# HydraBus_1_0_Rev1_1.net
KiCad netlist of a schematic drawn in EAGLE
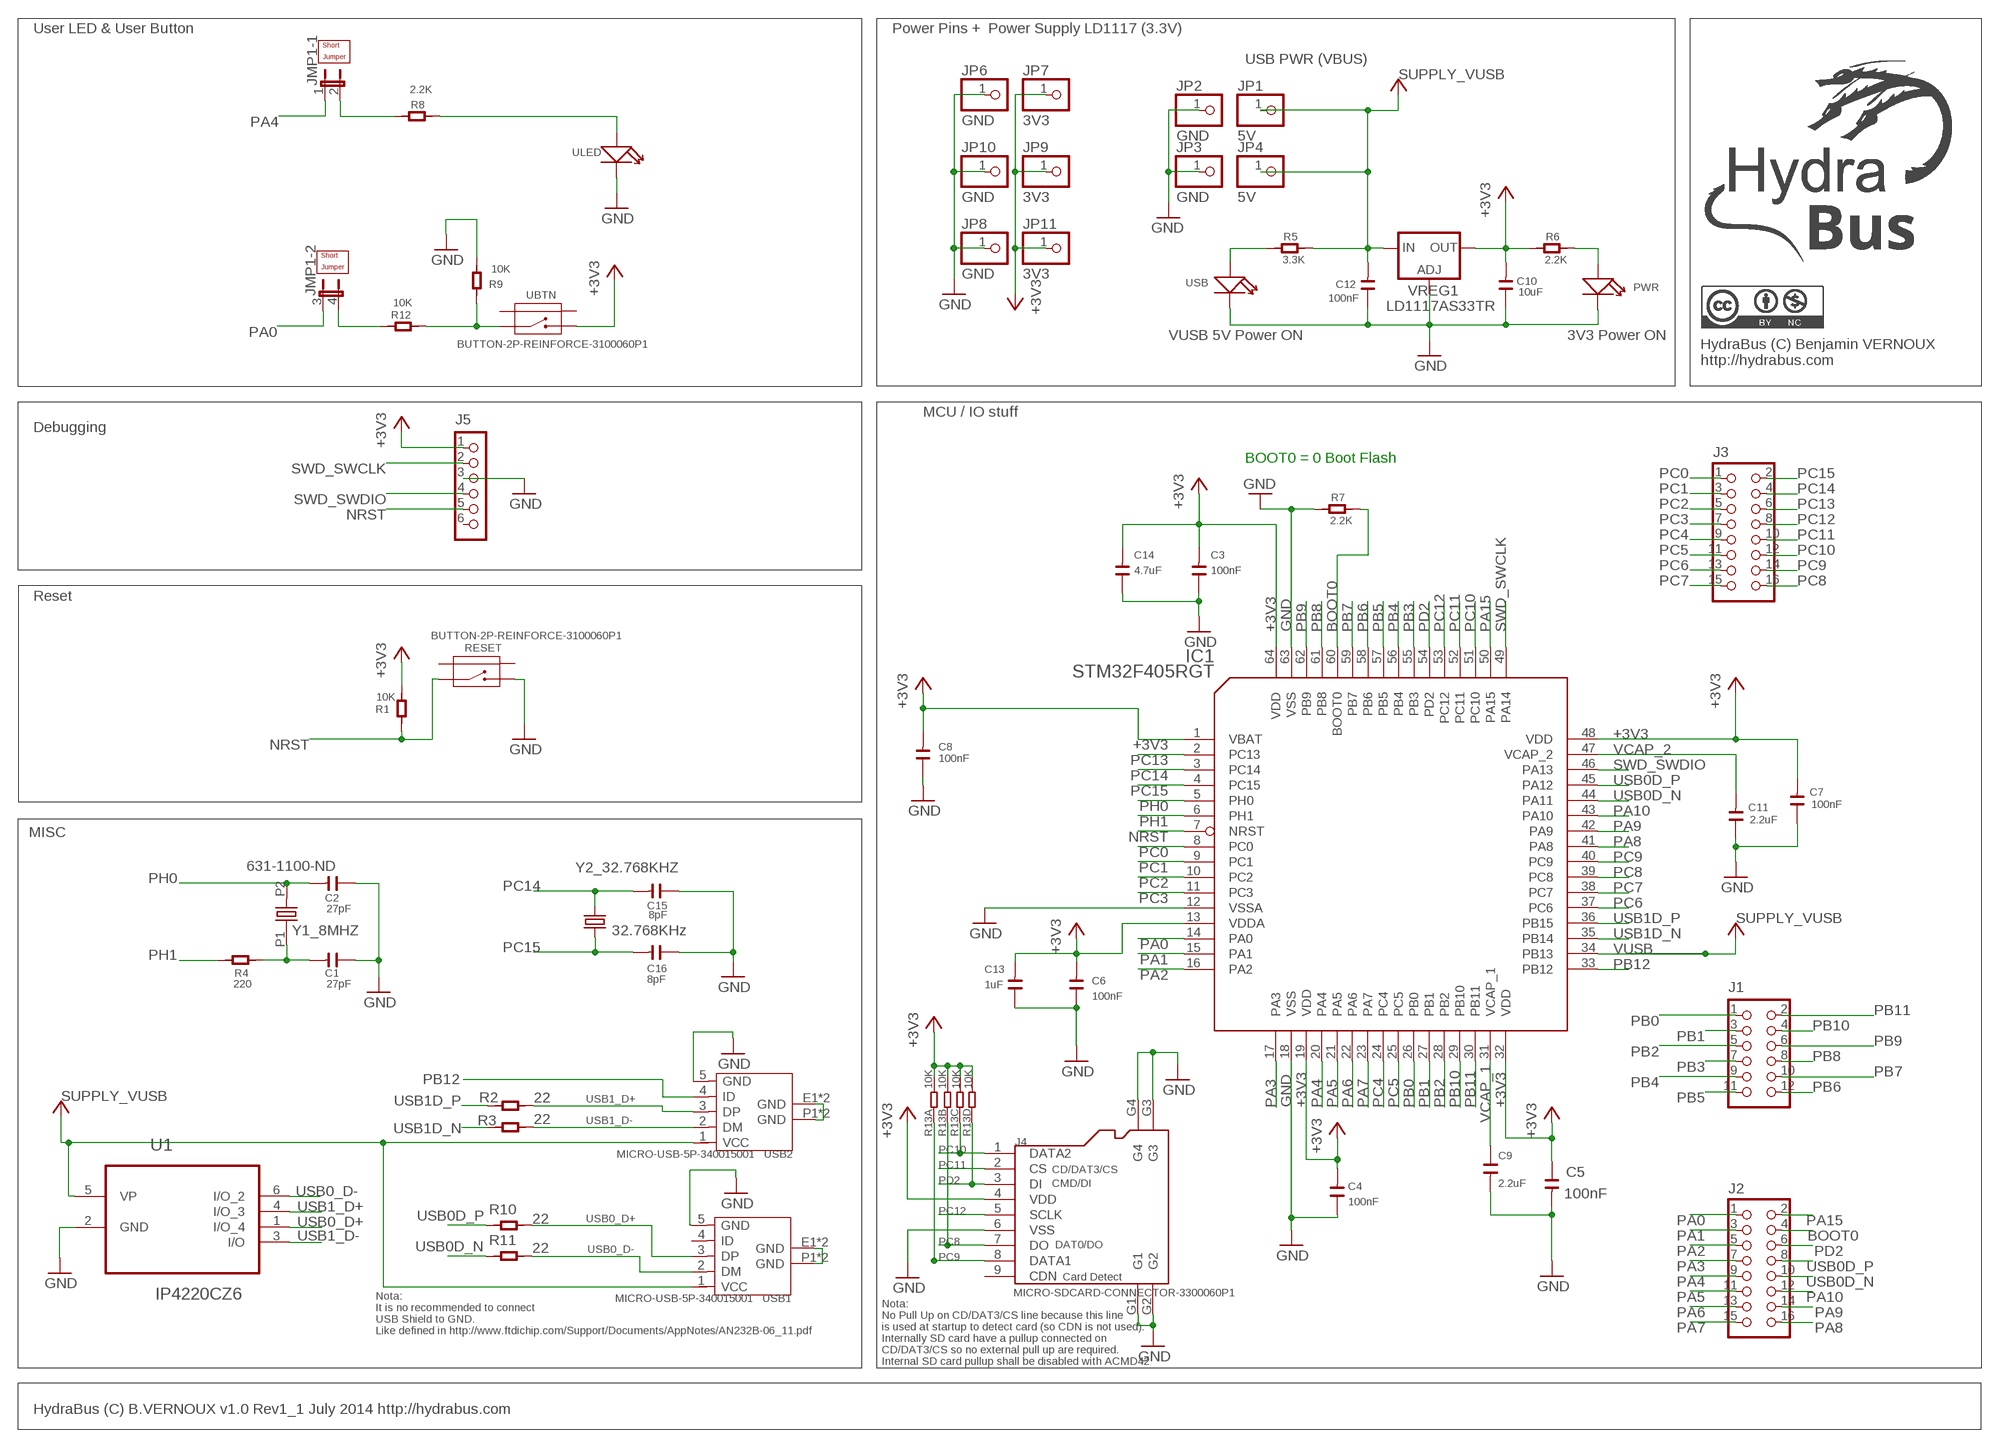
[diagram p0: schematic, sheet 1]

(export (version "E")
  (design (tool "Eeschema 10.0.6"))
  (components
    (comp (ref "C1")
      (value "27pF")
      (footprint "eagle-import:C0603")
      (libsource (lib "eagle-import") (part "C-0603"))
    )
    (comp (ref "C2")
      (value "27pF")
      (footprint "eagle-import:C0603")
      (libsource (lib "eagle-import") (part "C-0603"))
    )
    (comp (ref "C3")
      (value "100nF")
      (footprint "eagle-import:C0603")
      (libsource (lib "eagle-import") (part "C-0603"))
    )
    (comp (ref "C4")
      (value "100nF")
      (footprint "eagle-import:C0603")
      (libsource (lib "eagle-import") (part "C-0603"))
    )
    (comp (ref "C5")
      (value "100nF")
      (footprint "eagle-import:C0603")
      (libsource (lib "eagle-import") (part "C-0603"))
    )
    (comp (ref "C6")
      (value "100nF")
      (footprint "eagle-import:C0603")
      (libsource (lib "eagle-import") (part "C-0603"))
    )
    (comp (ref "C7")
      (value "100nF")
      (footprint "eagle-import:C0603")
      (libsource (lib "eagle-import") (part "C-0603"))
    )
    (comp (ref "C8")
      (value "100nF")
      (footprint "eagle-import:C0603")
      (libsource (lib "eagle-import") (part "C-0603"))
    )
    (comp (ref "C9")
      (value "2.2uF")
      (footprint "eagle-import:C0603")
      (libsource (lib "eagle-import") (part "C-0603"))
    )
    (comp (ref "C10")
      (value "10uF")
      (footprint "eagle-import:C0805")
      (libsource (lib "eagle-import") (part "C-0805"))
    )
    (comp (ref "C11")
      (value "2.2uF")
      (footprint "eagle-import:C0603")
      (libsource (lib "eagle-import") (part "C-0603"))
    )
    (comp (ref "C12")
      (value "100nF")
      (footprint "eagle-import:C0603")
      (libsource (lib "eagle-import") (part "C-0603"))
    )
    (comp (ref "C13")
      (value "1uF")
      (footprint "eagle-import:C0603")
      (libsource (lib "eagle-import") (part "C-0603"))
    )
    (comp (ref "C14")
      (value "4.7uF")
      (footprint "eagle-import:C0603")
      (libsource (lib "eagle-import") (part "C-0603"))
    )
    (comp (ref "C15")
      (value "8pF")
      (footprint "eagle-import:C0603")
      (libsource (lib "eagle-import") (part "C-0603"))
    )
    (comp (ref "C16")
      (value "8pF")
      (footprint "eagle-import:C0603")
      (libsource (lib "eagle-import") (part "C-0603"))
    )
    (comp (ref "IC1")
      (value "STM32F405RGT")
      (footprint "eagle-import:LQFP64")
      (libsource (lib "eagle-import") (part "STM32F405RTG"))
    )
    (comp (ref "J1")
      (value "CON_HEADER_2X06")
      (footprint "eagle-import:M2X6")
      (libsource (lib "eagle-import") (part "CON_HEADER_2X06"))
    )
    (comp (ref "J2")
      (value "CON_HEADER_2X08")
      (footprint "eagle-import:M2X8")
      (libsource (lib "eagle-import") (part "CON_HEADER_2X08"))
    )
    (comp (ref "J3")
      (value "CON_HEADER_2X08")
      (footprint "eagle-import:M2X8")
      (libsource (lib "eagle-import") (part "CON_HEADER_2X08"))
    )
    (comp (ref "J4")
      (value "MICRO-SDCARD-CONNECTOR-3300060P1")
      (footprint "eagle-import:9P-SMD-W-RING")
      (libsource (lib "eagle-import") (part "MICRO-SDCARD-CONNECTOR-3300060P1"))
    )
    (comp (ref "J5")
      (value "CON_HEADER_1X06-PTH")
      (footprint "eagle-import:M1X6")
      (libsource (lib "eagle-import") (part "CON_HEADER_1X06-PTH"))
    )
    (comp (ref "JMP1")
      (value "JP2QE")
      (footprint "eagle-import:JP2Q")
      (libsource (lib "eagle-import") (part "JP2QE"))
    )
    (comp (ref "JMP_UBTN")
      (value "SHORT-JUMPER-2P-3460440P1")
      (footprint "eagle-import:2P-2.54")
      (libsource (lib "eagle-import") (part "SHORT-JUMPER-2P-3460440P1"))
    )
    (comp (ref "JMP_ULED")
      (value "SHORT-JUMPER-2P-3460440P1")
      (footprint "eagle-import:2P-2.54")
      (libsource (lib "eagle-import") (part "SHORT-JUMPER-2P-3460440P1"))
    )
    (comp (ref "JP1")
      (value "5V")
      (footprint "eagle-import:1X01")
      (libsource (lib "eagle-import") (part "PINHD-1X1"))
    )
    (comp (ref "JP2")
      (value "GND")
      (footprint "eagle-import:1X01")
      (libsource (lib "eagle-import") (part "PINHD-1X1"))
    )
    (comp (ref "JP3")
      (value "GND")
      (footprint "eagle-import:1X01")
      (libsource (lib "eagle-import") (part "PINHD-1X1"))
    )
    (comp (ref "JP4")
      (value "5V")
      (footprint "eagle-import:1X01")
      (libsource (lib "eagle-import") (part "PINHD-1X1"))
    )
    (comp (ref "JP6")
      (value "GND")
      (footprint "eagle-import:1X01")
      (libsource (lib "eagle-import") (part "PINHD-1X1"))
    )
    (comp (ref "JP7")
      (value "3V3")
      (footprint "eagle-import:1X01")
      (libsource (lib "eagle-import") (part "PINHD-1X1"))
    )
    (comp (ref "JP8")
      (value "GND")
      (footprint "eagle-import:1X01")
      (libsource (lib "eagle-import") (part "PINHD-1X1"))
    )
    (comp (ref "JP9")
      (value "3V3")
      (footprint "eagle-import:1X01")
      (libsource (lib "eagle-import") (part "PINHD-1X1"))
    )
    (comp (ref "JP10")
      (value "GND")
      (footprint "eagle-import:1X01")
      (libsource (lib "eagle-import") (part "PINHD-1X1"))
    )
    (comp (ref "JP11")
      (value "3V3")
      (footprint "eagle-import:1X01")
      (libsource (lib "eagle-import") (part "PINHD-1X1"))
    )
    (comp (ref "PWR")
      (value "LED")
      (footprint "eagle-import:LED0603")
      (libsource (lib "eagle-import") (part "LED"))
    )
    (comp (ref "R1")
      (value "10K")
      (footprint "eagle-import:R0603")
      (libsource (lib "eagle-import") (part "R-0603"))
    )
    (comp (ref "R2")
      (value "22")
      (footprint "eagle-import:R0603")
      (libsource (lib "eagle-import") (part "R-0603"))
    )
    (comp (ref "R3")
      (value "22")
      (footprint "eagle-import:R0603")
      (libsource (lib "eagle-import") (part "R-0603"))
    )
    (comp (ref "R4")
      (value "220")
      (footprint "eagle-import:R0603")
      (libsource (lib "eagle-import") (part "R-0603"))
    )
    (comp (ref "R5")
      (value "3.3K")
      (footprint "eagle-import:R0603")
      (libsource (lib "eagle-import") (part "R-0603"))
    )
    (comp (ref "R6")
      (value "2.2K")
      (footprint "eagle-import:R0603")
      (libsource (lib "eagle-import") (part "R-0603"))
    )
    (comp (ref "R7")
      (value "2.2K")
      (footprint "eagle-import:R0603")
      (libsource (lib "eagle-import") (part "R-0603"))
    )
    (comp (ref "R8")
      (value "2.2K")
      (footprint "eagle-import:R0603")
      (libsource (lib "eagle-import") (part "R-0603"))
    )
    (comp (ref "R9")
      (value "10K")
      (footprint "eagle-import:R0603")
      (libsource (lib "eagle-import") (part "R-0603"))
    )
    (comp (ref "R10")
      (value "22")
      (footprint "eagle-import:R0603")
      (libsource (lib "eagle-import") (part "R-0603"))
    )
    (comp (ref "R11")
      (value "22")
      (footprint "eagle-import:R0603")
      (libsource (lib "eagle-import") (part "R-0603"))
    )
    (comp (ref "R12")
      (value "10K")
      (footprint "eagle-import:R0603")
      (libsource (lib "eagle-import") (part "R-0603"))
    )
    (comp (ref "R13")
      (value "10K")
      (footprint "eagle-import:R1206-8")
      (fields (field (name "OPL") "0040070P1 SMD RES ARRAY 10K OHM 4 RES 1206"))
      (libsource (lib "eagle-import") (part "R-4R"))
    )
    (comp (ref "RESET")
      (value "BUTTON-2P-REINFORCE-3100060P1")
      (footprint "eagle-import:4P-SMD-7.0X3.5X3.5H-90D")
      (libsource (lib "eagle-import") (part "BUTTON-2P-REINFORCE-3100060P1"))
    )
    (comp (ref "U1")
      (value "IP4220CZ6")
      (footprint "eagle-import:SOT95P275X110-6N")
      (libsource (lib "eagle-import") (part "IP4220CZ6"))
    )
    (comp (ref "UBTN")
      (value "BUTTON-2P-REINFORCE-3100060P1")
      (footprint "eagle-import:4P-SMD-7.0X3.5X3.5H-90D")
      (libsource (lib "eagle-import") (part "BUTTON-2P-REINFORCE-3100060P1"))
    )
    (comp (ref "ULED")
      (value "LED")
      (footprint "eagle-import:LED0603")
      (libsource (lib "eagle-import") (part "LED"))
    )
    (comp (ref "USB")
      (value "LED")
      (footprint "eagle-import:LED0603")
      (libsource (lib "eagle-import") (part "LED"))
    )
    (comp (ref "USB1")
      (value "MICRO-USB-5P-340015001")
      (footprint "eagle-import:B-SMD-5P")
      (libsource (lib "eagle-import") (part "MICRO-USB-5P-340015001"))
    )
    (comp (ref "USB2")
      (value "MICRO-USB-5P-340015001")
      (footprint "eagle-import:B-SMD-5P")
      (libsource (lib "eagle-import") (part "MICRO-USB-5P-340015001"))
    )
    (comp (ref "VREG1")
      (value "LD1117AS33TR")
      (footprint "eagle-import:SOT223")
      (libsource (lib "eagle-import") (part "LD117A?S33TR"))
    )
    (comp (ref "Y1_8MHZ")
      (value "631-1100-ND")
      (footprint "eagle-import:HC-49U-PTH")
      (libsource (lib "eagle-import") (part "OSC-XTAL-HC-49U-PTH"))
    )
    (comp (ref "Y2_32.768KHZ")
      (value "32.768KHz")
      (footprint "eagle-import:TC38H")
      (libsource (lib "eagle-import") (part "CRYSTALTC38H"))
    )
  )
  (nets
    (net (code "1") (name "+3V3") (class "Default")
      (node (ref "C10") (pin "1") (pinfunction "1_1") (pintype "bidirectional"))
      (node (ref "C13") (pin "1") (pinfunction "1_1") (pintype "bidirectional"))
      (node (ref "C14") (pin "1") (pinfunction "1_1") (pintype "bidirectional"))
      (node (ref "C3") (pin "1") (pinfunction "1_1") (pintype "bidirectional"))
      (node (ref "C4") (pin "1") (pinfunction "1_1") (pintype "bidirectional"))
      (node (ref "C5") (pin "2") (pinfunction "2_2") (pintype "bidirectional"))
      (node (ref "C6") (pin "1") (pinfunction "1_1") (pintype "bidirectional"))
      (node (ref "C7") (pin "1") (pinfunction "1_1") (pintype "bidirectional"))
      (node (ref "C8") (pin "1") (pinfunction "1_1") (pintype "bidirectional"))
      (node (ref "IC1") (pin "1") (pinfunction "VBAT_1") (pintype "power_in"))
      (node (ref "IC1") (pin "13") (pinfunction "VDDA_13") (pintype "power_in"))
      (node (ref "IC1") (pin "19") (pinfunction "VDD_19") (pintype "power_in"))
      (node (ref "IC1") (pin "32") (pinfunction "VDD_32") (pintype "power_in"))
      (node (ref "IC1") (pin "48") (pinfunction "VDD_48") (pintype "power_in"))
      (node (ref "IC1") (pin "64") (pinfunction "VDD_64") (pintype "power_in"))
      (node (ref "J4") (pin "4") (pinfunction "VDD_4") (pintype "bidirectional"))
      (node (ref "J5") (pin "1") (pinfunction "1_1") (pintype "bidirectional"))
      (node (ref "JP11") (pin "1") (pinfunction "1_1") (pintype "passive"))
      (node (ref "JP7") (pin "1") (pinfunction "1_1") (pintype "passive"))
      (node (ref "JP9") (pin "1") (pinfunction "1_1") (pintype "passive"))
      (node (ref "R1") (pin "2") (pinfunction "2_2") (pintype "bidirectional"))
      (node (ref "R13") (pin "5") (pinfunction "2_5") (pintype "passive"))
      (node (ref "R13") (pin "6") (pinfunction "2_6") (pintype "passive"))
      (node (ref "R13") (pin "7") (pinfunction "2_7") (pintype "passive"))
      (node (ref "R13") (pin "8") (pinfunction "2_8") (pintype "passive"))
      (node (ref "R6") (pin "2") (pinfunction "2_2") (pintype "bidirectional"))
      (node (ref "UBTN") (pin "2") (pinfunction "2_2") (pintype "bidirectional"))
      (node (ref "VREG1") (pin "4") (pinfunction "OUT_4") (pintype "passive"))
    )
    (net (code "2") (name "/BOOT0") (class "Default")
      (node (ref "IC1") (pin "60") (pinfunction "BOOT0_60") (pintype "bidirectional"))
      (node (ref "J2") (pin "4") (pinfunction "4_4") (pintype "passive"))
      (node (ref "R7") (pin "1") (pinfunction "1_1") (pintype "bidirectional"))
    )
    (net (code "3") (name "/NRST") (class "Default")
      (node (ref "IC1") (pin "7") (pinfunction "NRST_7") (pintype "input"))
      (node (ref "J5") (pin "5") (pinfunction "5_5") (pintype "passive"))
      (node (ref "R1") (pin "1") (pinfunction "1_1") (pintype "bidirectional"))
      (node (ref "RESET") (pin "1") (pinfunction "1_1") (pintype "bidirectional"))
    )
    (net (code "4") (name "/PA0") (class "Default")
      (node (ref "IC1") (pin "14") (pinfunction "PA0_14") (pintype "bidirectional"))
      (node (ref "J2") (pin "1") (pinfunction "1_1") (pintype "passive"))
      (node (ref "JMP1") (pin "3") (pinfunction "1_3") (pintype "passive"))
    )
    (net (code "5") (name "/PA1") (class "Default")
      (node (ref "IC1") (pin "15") (pinfunction "PA1_15") (pintype "bidirectional"))
      (node (ref "J2") (pin "3") (pinfunction "3_3") (pintype "passive"))
    )
    (net (code "6") (name "/PA2") (class "Default")
      (node (ref "IC1") (pin "16") (pinfunction "PA2_16") (pintype "bidirectional"))
      (node (ref "J2") (pin "5") (pinfunction "5_5") (pintype "passive"))
    )
    (net (code "7") (name "/PA3") (class "Default")
      (node (ref "IC1") (pin "17") (pinfunction "PA3_17") (pintype "bidirectional"))
      (node (ref "J2") (pin "7") (pinfunction "7_7") (pintype "passive"))
    )
    (net (code "8") (name "/PA4") (class "Default")
      (node (ref "IC1") (pin "20") (pinfunction "PA4_20") (pintype "bidirectional"))
      (node (ref "J2") (pin "9") (pinfunction "9_9") (pintype "passive"))
      (node (ref "JMP1") (pin "1") (pinfunction "1_1") (pintype "passive"))
    )
    (net (code "9") (name "/PA5") (class "Default")
      (node (ref "IC1") (pin "21") (pinfunction "PA5_21") (pintype "bidirectional"))
      (node (ref "J2") (pin "11") (pinfunction "11_11") (pintype "passive"))
    )
    (net (code "10") (name "/PA6") (class "Default")
      (node (ref "IC1") (pin "22") (pinfunction "PA6_22") (pintype "bidirectional"))
      (node (ref "J2") (pin "13") (pinfunction "13_13") (pintype "passive"))
    )
    (net (code "11") (name "/PA7") (class "Default")
      (node (ref "IC1") (pin "23") (pinfunction "PA7_23") (pintype "bidirectional"))
      (node (ref "J2") (pin "15") (pinfunction "15_15") (pintype "passive"))
    )
    (net (code "12") (name "/PA8") (class "Default")
      (node (ref "IC1") (pin "41") (pinfunction "PA8_41") (pintype "bidirectional"))
      (node (ref "J2") (pin "16") (pinfunction "16_16") (pintype "passive"))
    )
    (net (code "13") (name "/PA9") (class "Default")
      (node (ref "IC1") (pin "42") (pinfunction "PA9_42") (pintype "bidirectional"))
      (node (ref "J2") (pin "14") (pinfunction "14_14") (pintype "passive"))
    )
    (net (code "14") (name "/PA10") (class "Default")
      (node (ref "IC1") (pin "43") (pinfunction "PA10_43") (pintype "bidirectional"))
      (node (ref "J2") (pin "12") (pinfunction "12_12") (pintype "passive"))
    )
    (net (code "15") (name "/PA15") (class "Default")
      (node (ref "IC1") (pin "50") (pinfunction "PA15_50") (pintype "bidirectional"))
      (node (ref "J2") (pin "2") (pinfunction "2_2") (pintype "passive"))
    )
    (net (code "16") (name "/PB0") (class "Default")
      (node (ref "IC1") (pin "26") (pinfunction "PB0_26") (pintype "bidirectional"))
      (node (ref "J1") (pin "1") (pinfunction "1_1") (pintype "passive"))
    )
    (net (code "17") (name "/PB1") (class "Default")
      (node (ref "IC1") (pin "27") (pinfunction "PB1_27") (pintype "bidirectional"))
      (node (ref "J1") (pin "3") (pinfunction "3_3") (pintype "passive"))
    )
    (net (code "18") (name "/PB2") (class "Default")
      (node (ref "IC1") (pin "28") (pinfunction "PB2_28") (pintype "bidirectional"))
      (node (ref "J1") (pin "5") (pinfunction "5_5") (pintype "passive"))
    )
    (net (code "19") (name "/PB3") (class "Default")
      (node (ref "IC1") (pin "55") (pinfunction "PB3_55") (pintype "bidirectional"))
      (node (ref "J1") (pin "7") (pinfunction "7_7") (pintype "passive"))
    )
    (net (code "20") (name "/PB4") (class "Default")
      (node (ref "IC1") (pin "56") (pinfunction "PB4_56") (pintype "bidirectional"))
      (node (ref "J1") (pin "9") (pinfunction "9_9") (pintype "passive"))
    )
    (net (code "21") (name "/PB5") (class "Default")
      (node (ref "IC1") (pin "57") (pinfunction "PB5_57") (pintype "bidirectional"))
      (node (ref "J1") (pin "11") (pinfunction "11_11") (pintype "passive"))
    )
    (net (code "22") (name "/PB6") (class "Default")
      (node (ref "IC1") (pin "58") (pinfunction "PB6_58") (pintype "bidirectional"))
      (node (ref "J1") (pin "12") (pinfunction "12_12") (pintype "passive"))
    )
    (net (code "23") (name "/PB7") (class "Default")
      (node (ref "IC1") (pin "59") (pinfunction "PB7_59") (pintype "bidirectional"))
      (node (ref "J1") (pin "10") (pinfunction "10_10") (pintype "passive"))
    )
    (net (code "24") (name "/PB8") (class "Default")
      (node (ref "IC1") (pin "61") (pinfunction "PB8_61") (pintype "bidirectional"))
      (node (ref "J1") (pin "8") (pinfunction "8_8") (pintype "passive"))
    )
    (net (code "25") (name "/PB9") (class "Default")
      (node (ref "IC1") (pin "62") (pinfunction "PB9_62") (pintype "bidirectional"))
      (node (ref "J1") (pin "6") (pinfunction "6_6") (pintype "passive"))
    )
    (net (code "26") (name "/PB10") (class "Default")
      (node (ref "IC1") (pin "29") (pinfunction "PB10_29") (pintype "bidirectional"))
      (node (ref "J1") (pin "4") (pinfunction "4_4") (pintype "passive"))
    )
    (net (code "27") (name "/PB11") (class "Default")
      (node (ref "IC1") (pin "30") (pinfunction "PB11_30") (pintype "bidirectional"))
      (node (ref "J1") (pin "2") (pinfunction "2_2") (pintype "passive"))
    )
    (net (code "28") (name "/PB12") (class "Default")
      (node (ref "IC1") (pin "33") (pinfunction "PB12_33") (pintype "bidirectional"))
      (node (ref "USB2") (pin "4") (pinfunction "ID_4") (pintype "bidirectional"))
    )
    (net (code "29") (name "/PC0") (class "Default")
      (node (ref "IC1") (pin "8") (pinfunction "PC0_8") (pintype "bidirectional"))
      (node (ref "J3") (pin "1") (pinfunction "1_1") (pintype "passive"))
    )
    (net (code "30") (name "/PC1") (class "Default")
      (node (ref "IC1") (pin "9") (pinfunction "PC1_9") (pintype "bidirectional"))
      (node (ref "J3") (pin "3") (pinfunction "3_3") (pintype "passive"))
    )
    (net (code "31") (name "/PC2") (class "Default")
      (node (ref "IC1") (pin "10") (pinfunction "PC2_10") (pintype "bidirectional"))
      (node (ref "J3") (pin "5") (pinfunction "5_5") (pintype "passive"))
    )
    (net (code "32") (name "/PC3") (class "Default")
      (node (ref "IC1") (pin "11") (pinfunction "PC3_11") (pintype "bidirectional"))
      (node (ref "J3") (pin "7") (pinfunction "7_7") (pintype "passive"))
    )
    (net (code "33") (name "/PC4") (class "Default")
      (node (ref "IC1") (pin "24") (pinfunction "PC4_24") (pintype "bidirectional"))
      (node (ref "J3") (pin "9") (pinfunction "9_9") (pintype "passive"))
    )
    (net (code "34") (name "/PC5") (class "Default")
      (node (ref "IC1") (pin "25") (pinfunction "PC5_25") (pintype "bidirectional"))
      (node (ref "J3") (pin "11") (pinfunction "11_11") (pintype "passive"))
    )
    (net (code "35") (name "/PC6") (class "Default")
      (node (ref "IC1") (pin "37") (pinfunction "PC6_37") (pintype "bidirectional"))
      (node (ref "J3") (pin "13") (pinfunction "13_13") (pintype "passive"))
    )
    (net (code "36") (name "/PC7") (class "Default")
      (node (ref "IC1") (pin "38") (pinfunction "PC7_38") (pintype "bidirectional"))
      (node (ref "J3") (pin "15") (pinfunction "15_15") (pintype "passive"))
    )
    (net (code "37") (name "/PC8") (class "Default")
      (node (ref "IC1") (pin "39") (pinfunction "PC8_39") (pintype "bidirectional"))
      (node (ref "J3") (pin "16") (pinfunction "16_16") (pintype "passive"))
      (node (ref "J4") (pin "7") (pinfunction "DO_7") (pintype "bidirectional"))
      (node (ref "R13") (pin "2") (pinfunction "1_2") (pintype "passive"))
    )
    (net (code "38") (name "/PC9") (class "Default")
      (node (ref "IC1") (pin "40") (pinfunction "PC9_40") (pintype "bidirectional"))
      (node (ref "J3") (pin "14") (pinfunction "14_14") (pintype "passive"))
      (node (ref "J4") (pin "8") (pinfunction "DATA1_8") (pintype "bidirectional"))
      (node (ref "R13") (pin "1") (pinfunction "1_1") (pintype "passive"))
    )
    (net (code "39") (name "/PC10") (class "Default")
      (node (ref "IC1") (pin "51") (pinfunction "PC10_51") (pintype "bidirectional"))
      (node (ref "J3") (pin "12") (pinfunction "12_12") (pintype "passive"))
      (node (ref "J4") (pin "1") (pinfunction "DATA2_1") (pintype "bidirectional"))
      (node (ref "R13") (pin "3") (pinfunction "1_3") (pintype "passive"))
    )
    (net (code "40") (name "/PC11") (class "Default")
      (node (ref "IC1") (pin "52") (pinfunction "PC11_52") (pintype "bidirectional"))
      (node (ref "J3") (pin "10") (pinfunction "10_10") (pintype "passive"))
      (node (ref "J4") (pin "2") (pinfunction "CS_2") (pintype "bidirectional"))
    )
    (net (code "41") (name "/PC12") (class "Default")
      (node (ref "IC1") (pin "53") (pinfunction "PC12_53") (pintype "bidirectional"))
      (node (ref "J3") (pin "8") (pinfunction "8_8") (pintype "passive"))
      (node (ref "J4") (pin "5") (pinfunction "SCLK_5") (pintype "bidirectional"))
    )
    (net (code "42") (name "/PC13") (class "Default")
      (node (ref "IC1") (pin "2") (pinfunction "PC13_2") (pintype "bidirectional"))
      (node (ref "J3") (pin "6") (pinfunction "6_6") (pintype "passive"))
    )
    (net (code "43") (name "/PC14") (class "Default")
      (node (ref "C15") (pin "1") (pinfunction "1_1") (pintype "bidirectional"))
      (node (ref "IC1") (pin "3") (pinfunction "PC14_3") (pintype "bidirectional"))
      (node (ref "J3") (pin "4") (pinfunction "4_4") (pintype "passive"))
      (node (ref "Y2_32.768KHZ") (pin "2") (pinfunction "2_2") (pintype "passive"))
    )
    (net (code "44") (name "/PC15") (class "Default")
      (node (ref "C16") (pin "1") (pinfunction "1_1") (pintype "bidirectional"))
      (node (ref "IC1") (pin "4") (pinfunction "PC15_4") (pintype "bidirectional"))
      (node (ref "J3") (pin "2") (pinfunction "2_2") (pintype "passive"))
      (node (ref "Y2_32.768KHZ") (pin "1") (pinfunction "1_1") (pintype "passive"))
    )
    (net (code "45") (name "/PD2") (class "Default")
      (node (ref "IC1") (pin "54") (pinfunction "PD2_54") (pintype "bidirectional"))
      (node (ref "J2") (pin "6") (pinfunction "6_6") (pintype "passive"))
      (node (ref "J4") (pin "3") (pinfunction "DI_3") (pintype "bidirectional"))
      (node (ref "R13") (pin "4") (pinfunction "1_4") (pintype "passive"))
    )
    (net (code "46") (name "/PH0") (class "Default")
      (node (ref "C2") (pin "1") (pinfunction "1_1") (pintype "bidirectional"))
      (node (ref "IC1") (pin "5") (pinfunction "PH0_5") (pintype "bidirectional"))
      (node (ref "Y1_8MHZ") (pin "P2") (pinfunction "2_P2") (pintype "passive"))
    )
    (net (code "47") (name "/PH1") (class "Default")
      (node (ref "IC1") (pin "6") (pinfunction "PH1_6") (pintype "bidirectional"))
      (node (ref "R4") (pin "2") (pinfunction "2_2") (pintype "bidirectional"))
    )
    (net (code "48") (name "/SWD_SWCLK") (class "Default")
      (node (ref "IC1") (pin "49") (pinfunction "PA14_49") (pintype "bidirectional"))
      (node (ref "J5") (pin "2") (pinfunction "2_2") (pintype "bidirectional"))
    )
    (net (code "49") (name "/SWD_SWDIO") (class "Default")
      (node (ref "IC1") (pin "46") (pinfunction "PA13_46") (pintype "bidirectional"))
      (node (ref "J5") (pin "4") (pinfunction "4_4") (pintype "passive"))
    )
    (net (code "50") (name "/USB0D_N") (class "Default")
      (node (ref "IC1") (pin "44") (pinfunction "PA11_44") (pintype "bidirectional"))
      (node (ref "J2") (pin "10") (pinfunction "10_10") (pintype "passive"))
      (node (ref "R11") (pin "2") (pinfunction "2_2") (pintype "bidirectional"))
    )
    (net (code "51") (name "/USB0D_P") (class "Default")
      (node (ref "IC1") (pin "45") (pinfunction "PA12_45") (pintype "bidirectional"))
      (node (ref "J2") (pin "8") (pinfunction "8_8") (pintype "passive"))
      (node (ref "R10") (pin "2") (pinfunction "2_2") (pintype "bidirectional"))
    )
    (net (code "52") (name "/USB0_D+") (class "Default")
      (node (ref "R10") (pin "1") (pinfunction "1_1") (pintype "bidirectional"))
      (node (ref "U1") (pin "1") (pinfunction "I/O_4_1") (pintype "bidirectional"))
      (node (ref "USB1") (pin "3") (pinfunction "DP_3") (pintype "bidirectional"))
    )
    (net (code "53") (name "/USB0_D-") (class "Default")
      (node (ref "R11") (pin "1") (pinfunction "1_1") (pintype "bidirectional"))
      (node (ref "U1") (pin "6") (pinfunction "I/O_2_6") (pintype "bidirectional"))
      (node (ref "USB1") (pin "2") (pinfunction "DM_2") (pintype "bidirectional"))
    )
    (net (code "54") (name "/USB1D_N") (class "Default")
      (node (ref "IC1") (pin "35") (pinfunction "PB14_35") (pintype "bidirectional"))
      (node (ref "R3") (pin "2") (pinfunction "2_2") (pintype "bidirectional"))
    )
    (net (code "55") (name "/USB1D_P") (class "Default")
      (node (ref "IC1") (pin "36") (pinfunction "PB15_36") (pintype "bidirectional"))
      (node (ref "R2") (pin "2") (pinfunction "2_2") (pintype "bidirectional"))
    )
    (net (code "56") (name "/USB1_D+") (class "Default")
      (node (ref "R2") (pin "1") (pinfunction "1_1") (pintype "bidirectional"))
      (node (ref "U1") (pin "4") (pinfunction "I/O_3_4") (pintype "bidirectional"))
      (node (ref "USB2") (pin "3") (pinfunction "DP_3") (pintype "bidirectional"))
    )
    (net (code "57") (name "/USB1_D-") (class "Default")
      (node (ref "R3") (pin "1") (pinfunction "1_1") (pintype "bidirectional"))
      (node (ref "U1") (pin "3") (pinfunction "I/O_3") (pintype "bidirectional"))
      (node (ref "USB2") (pin "2") (pinfunction "DM_2") (pintype "bidirectional"))
    )
    (net (code "58") (name "/VCAP_1") (class "Default")
      (node (ref "C9") (pin "2") (pinfunction "2_2") (pintype "bidirectional"))
      (node (ref "IC1") (pin "31") (pinfunction "VCAP_1_31") (pintype "passive"))
    )
    (net (code "59") (name "/VCAP_2") (class "Default")
      (node (ref "C11") (pin "1") (pinfunction "1_1") (pintype "bidirectional"))
      (node (ref "IC1") (pin "47") (pinfunction "VCAP_2_47") (pintype "passive"))
    )
    (net (code "60") (name "GND") (class "Default")
      (node (ref "C1") (pin "2") (pinfunction "2_2") (pintype "bidirectional"))
      (node (ref "C10") (pin "2") (pinfunction "2_2") (pintype "bidirectional"))
      (node (ref "C11") (pin "2") (pinfunction "2_2") (pintype "bidirectional"))
      (node (ref "C12") (pin "2") (pinfunction "2_2") (pintype "bidirectional"))
      (node (ref "C13") (pin "2") (pinfunction "2_2") (pintype "bidirectional"))
      (node (ref "C14") (pin "2") (pinfunction "2_2") (pintype "bidirectional"))
      (node (ref "C15") (pin "2") (pinfunction "2_2") (pintype "bidirectional"))
      (node (ref "C16") (pin "2") (pinfunction "2_2") (pintype "bidirectional"))
      (node (ref "C2") (pin "2") (pinfunction "2_2") (pintype "bidirectional"))
      (node (ref "C3") (pin "2") (pinfunction "2_2") (pintype "bidirectional"))
      (node (ref "C4") (pin "2") (pinfunction "2_2") (pintype "bidirectional"))
      (node (ref "C5") (pin "1") (pinfunction "1_1") (pintype "bidirectional"))
      (node (ref "C6") (pin "2") (pinfunction "2_2") (pintype "bidirectional"))
      (node (ref "C7") (pin "2") (pinfunction "2_2") (pintype "bidirectional"))
      (node (ref "C8") (pin "2") (pinfunction "2_2") (pintype "bidirectional"))
      (node (ref "C9") (pin "1") (pinfunction "1_1") (pintype "bidirectional"))
      (node (ref "IC1") (pin "12") (pinfunction "VSSA_12") (pintype "power_in"))
      (node (ref "IC1") (pin "18") (pinfunction "VSS_18") (pintype "power_in"))
      (node (ref "IC1") (pin "63") (pinfunction "VSS_63") (pintype "power_in"))
      (node (ref "J4") (pin "6") (pinfunction "VSS_6") (pintype "bidirectional"))
      (node (ref "J4") (pin "G1") (pinfunction "G1_G1") (pintype "bidirectional"))
      (node (ref "J4") (pin "G2") (pinfunction "G2_G2") (pintype "bidirectional"))
      (node (ref "J4") (pin "G3") (pinfunction "G3_G3") (pintype "bidirectional"))
      (node (ref "J4") (pin "G4") (pinfunction "G4_G4") (pintype "bidirectional"))
      (node (ref "J5") (pin "3") (pinfunction "3_3") (pintype "passive"))
      (node (ref "JP10") (pin "1") (pinfunction "1_1") (pintype "passive"))
      (node (ref "JP2") (pin "1") (pinfunction "1_1") (pintype "passive"))
      (node (ref "JP3") (pin "1") (pinfunction "1_1") (pintype "passive"))
      (node (ref "JP6") (pin "1") (pinfunction "1_1") (pintype "passive"))
      (node (ref "JP8") (pin "1") (pinfunction "1_1") (pintype "passive"))
      (node (ref "PWR") (pin "-") (pinfunction "-_-") (pintype "passive"))
      (node (ref "R7") (pin "2") (pinfunction "2_2") (pintype "bidirectional"))
      (node (ref "R9") (pin "2") (pinfunction "2_2") (pintype "bidirectional"))
      (node (ref "RESET") (pin "2") (pinfunction "2_2") (pintype "bidirectional"))
      (node (ref "U1") (pin "2") (pinfunction "GND_2") (pintype "passive"))
      (node (ref "ULED") (pin "-") (pinfunction "-_-") (pintype "passive"))
      (node (ref "USB") (pin "-") (pinfunction "-_-") (pintype "passive"))
      (node (ref "USB1") (pin "5") (pinfunction "GND_5") (pintype "bidirectional"))
      (node (ref "USB2") (pin "5") (pinfunction "GND_5") (pintype "bidirectional"))
      (node (ref "VREG1") (pin "1") (pinfunction "ADJ_1") (pintype "input"))
    )
    (net (code "61") (name "Net-(JMP1-Pad2)") (class "Default")
      (node (ref "JMP1") (pin "2") (pinfunction "2_2") (pintype "passive"))
      (node (ref "R8") (pin "2") (pinfunction "2_2") (pintype "bidirectional"))
    )
    (net (code "62") (name "Net-(JMP1B-2)") (class "Default")
      (node (ref "JMP1") (pin "4") (pinfunction "2_4") (pintype "passive"))
      (node (ref "R12") (pin "2") (pinfunction "2_2") (pintype "bidirectional"))
    )
    (net (code "63") (name "Net-(PWR-Pad+)") (class "Default")
      (node (ref "PWR") (pin "+") (pinfunction "+_+") (pintype "passive"))
      (node (ref "R6") (pin "1") (pinfunction "1_1") (pintype "bidirectional"))
    )
    (net (code "64") (name "Net-(R5-Pad2)") (class "Default")
      (node (ref "R5") (pin "2") (pinfunction "2_2") (pintype "bidirectional"))
      (node (ref "USB") (pin "+") (pinfunction "+_+") (pintype "passive"))
    )
    (net (code "65") (name "Net-(R8-Pad1)") (class "Default")
      (node (ref "R8") (pin "1") (pinfunction "1_1") (pintype "bidirectional"))
      (node (ref "ULED") (pin "+") (pinfunction "+_+") (pintype "passive"))
    )
    (net (code "66") (name "Net-(R12-Pad1)") (class "Default")
      (node (ref "R12") (pin "1") (pinfunction "1_1") (pintype "bidirectional"))
      (node (ref "R9") (pin "1") (pinfunction "1_1") (pintype "bidirectional"))
      (node (ref "UBTN") (pin "1") (pinfunction "1_1") (pintype "bidirectional"))
    )
    (net (code "67") (name "Net-(USB1-GND-PadE1)") (class "Default")
      (node (ref "USB1") (pin "E1") (pinfunction "GND_E1") (pintype "bidirectional"))
      (node (ref "USB1") (pin "E2") (pinfunction "GND_E2") (pintype "bidirectional"))
      (node (ref "USB1") (pin "P1") (pinfunction "GND_P1") (pintype "bidirectional"))
      (node (ref "USB1") (pin "P2") (pinfunction "GND_P2") (pintype "bidirectional"))
    )
    (net (code "68") (name "Net-(USB2-GND-PadE1)") (class "Default")
      (node (ref "USB2") (pin "E1") (pinfunction "GND_E1") (pintype "bidirectional"))
      (node (ref "USB2") (pin "E2") (pinfunction "GND_E2") (pintype "bidirectional"))
      (node (ref "USB2") (pin "P1") (pinfunction "GND_P1") (pintype "bidirectional"))
      (node (ref "USB2") (pin "P2") (pinfunction "GND_P2") (pintype "bidirectional"))
    )
    (net (code "69") (name "Net-(Y1_8MHZ-1)") (class "Default")
      (node (ref "C1") (pin "1") (pinfunction "1_1") (pintype "bidirectional"))
      (node (ref "R4") (pin "1") (pinfunction "1_1") (pintype "bidirectional"))
      (node (ref "Y1_8MHZ") (pin "P1") (pinfunction "1_P1") (pintype "passive"))
    )
    (net (code "70") (name "SUPPLY_VUSB") (class "Default")
      (node (ref "C12") (pin "1") (pinfunction "1_1") (pintype "bidirectional"))
      (node (ref "IC1") (pin "34") (pinfunction "PB13_34") (pintype "bidirectional"))
      (node (ref "JP1") (pin "1") (pinfunction "1_1") (pintype "passive"))
      (node (ref "JP4") (pin "1") (pinfunction "1_1") (pintype "passive"))
      (node (ref "R5") (pin "1") (pinfunction "1_1") (pintype "bidirectional"))
      (node (ref "U1") (pin "5") (pinfunction "VP_5") (pintype "power_in"))
      (node (ref "USB1") (pin "1") (pinfunction "VCC_1") (pintype "bidirectional"))
      (node (ref "USB2") (pin "1") (pinfunction "VCC_1") (pintype "bidirectional"))
      (node (ref "VREG1") (pin "3") (pinfunction "IN_3") (pintype "input"))
    )
    (net (code "71") (name "unconnected-(J4-CDN-Pad9)") (class "Default")
      (node (ref "J4") (pin "9") (pinfunction "CDN_9") (pintype "bidirectional"))
    )
    (net (code "72") (name "unconnected-(J5-Pad6)") (class "Default")
      (node (ref "J5") (pin "6") (pinfunction "6_6") (pintype "passive"))
    )
    (net (code "73") (name "unconnected-(RESET-PadS1)") (class "Default")
      (node (ref "RESET") (pin "S1") (pinfunction "S1_S1") (pintype "bidirectional"))
    )
    (net (code "74") (name "unconnected-(RESET-PadS2)") (class "Default")
      (node (ref "RESET") (pin "S2") (pinfunction "S2_S2") (pintype "bidirectional"))
    )
    (net (code "75") (name "unconnected-(UBTN-PadS1)") (class "Default")
      (node (ref "UBTN") (pin "S1") (pinfunction "S1_S1") (pintype "bidirectional"))
    )
    (net (code "76") (name "unconnected-(UBTN-PadS2)") (class "Default")
      (node (ref "UBTN") (pin "S2") (pinfunction "S2_S2") (pintype "bidirectional"))
    )
    (net (code "77") (name "unconnected-(USB1-ID-Pad4)") (class "Default")
      (node (ref "USB1") (pin "4") (pinfunction "ID_4") (pintype "bidirectional"))
    )
  )
)
